# lamloei_umo32c_r2_1.net
KiCad netlist of a schematic drawn in EAGLE
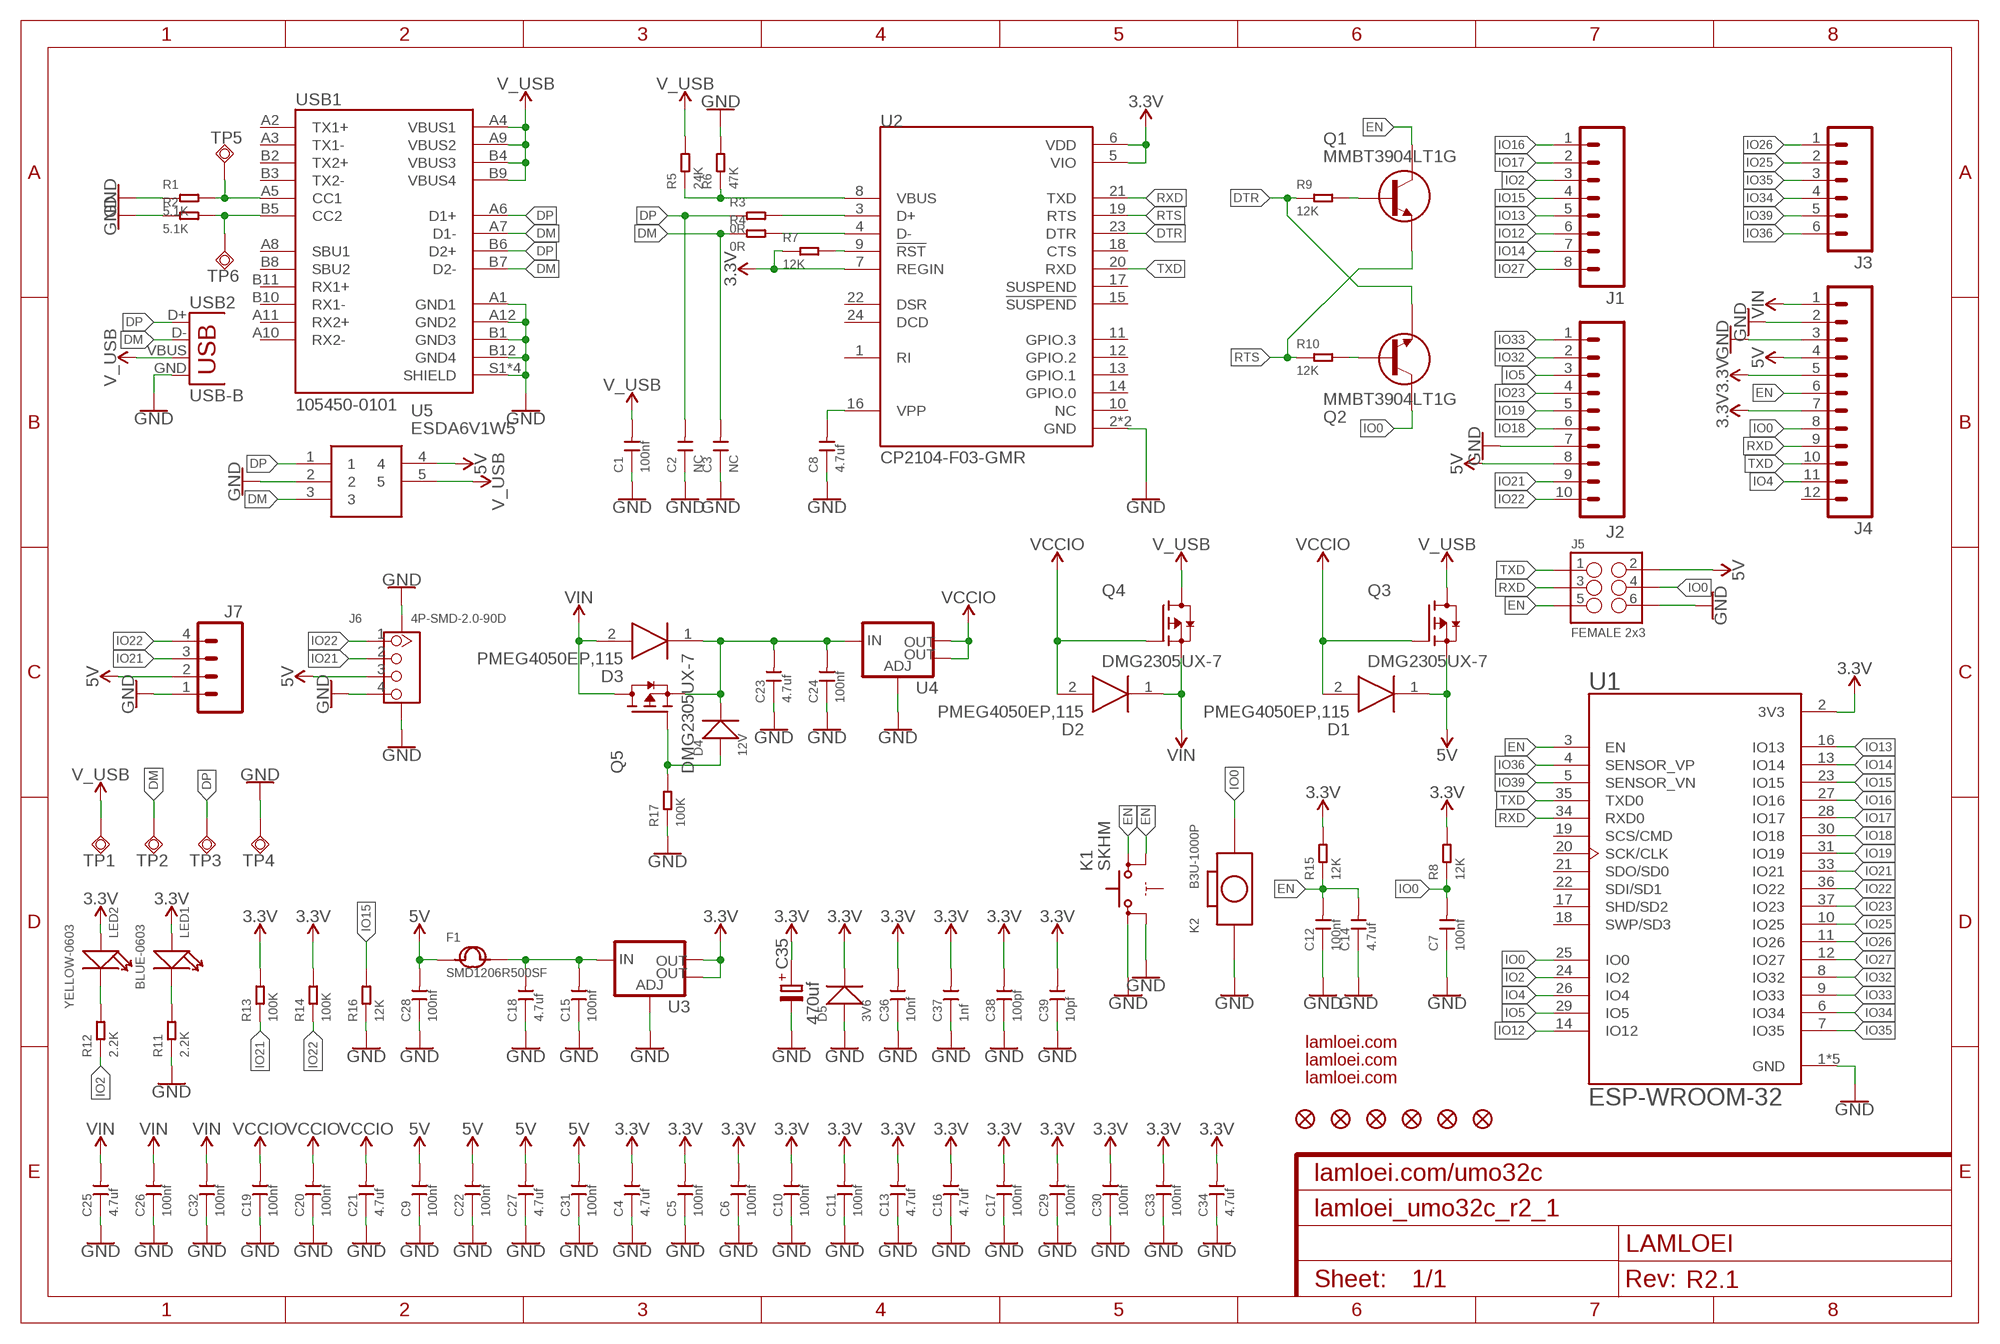
[diagram p0: schematic, sheet 1]

(export (version "E")
  (design (tool "Eeschema 10.0.6"))
  (components
    (comp (ref "C1")
      (value "100nf")
      (footprint "eagle-import:C0402")
      (fields (field (name "MPN") "CC0402KRX7R8BB104"))
      (libsource (lib "eagle-import") (part "CERAMIC-100NF-25V-10%-X7R(0402)"))
    )
    (comp (ref "C2")
      (value "NC")
      (footprint "eagle-import:C0402")
      (fields (field (name "MPN") "CC0402JRNPO9BN470"))
      (libsource (lib "eagle-import") (part "CERAMIC-47PF-50V-5%-NP0(0402)"))
    )
    (comp (ref "C3")
      (value "NC")
      (footprint "eagle-import:C0402")
      (fields (field (name "MPN") "CC0402JRNPO9BN470"))
      (libsource (lib "eagle-import") (part "CERAMIC-47PF-50V-5%-NP0(0402)"))
    )
    (comp (ref "C4")
      (value "4.7uf")
      (footprint "eagle-import:C0805")
      (fields (field (name "MPN") "CC0805KKX5R8BB106"))
      (libsource (lib "eagle-import") (part "CERAMIC-10UF-25V-10%-X5R(0805)"))
    )
    (comp (ref "C5")
      (value "100nf")
      (footprint "eagle-import:C0402")
      (fields (field (name "MPN") "CC0402KRX7R8BB104"))
      (libsource (lib "eagle-import") (part "CERAMIC-100NF-25V-10%-X7R(0402)"))
    )
    (comp (ref "C6")
      (value "100nf")
      (footprint "eagle-import:C0402")
      (fields (field (name "MPN") "CC0402KRX7R8BB104"))
      (libsource (lib "eagle-import") (part "CERAMIC-100NF-25V-10%-X7R(0402)"))
    )
    (comp (ref "C7")
      (value "100nf")
      (footprint "eagle-import:C0402")
      (fields (field (name "MPN") "CC0402KRX7R8BB104"))
      (libsource (lib "eagle-import") (part "CERAMIC-100NF-25V-10%-X7R(0402)"))
    )
    (comp (ref "C8")
      (value "4.7uf")
      (footprint "eagle-import:C0805")
      (fields (field (name "MPN") "CC0805KKX5R8BB106"))
      (libsource (lib "eagle-import") (part "CERAMIC-10UF-25V-10%-X5R(0805)"))
    )
    (comp (ref "C9")
      (value "100nf")
      (footprint "eagle-import:C0402")
      (fields (field (name "MPN") "CC0402KRX7R8BB104"))
      (libsource (lib "eagle-import") (part "CERAMIC-100NF-25V-10%-X7R(0402)"))
    )
    (comp (ref "C10")
      (value "100nf")
      (footprint "eagle-import:C0402")
      (fields (field (name "MPN") "CC0402KRX7R8BB104"))
      (libsource (lib "eagle-import") (part "CERAMIC-100NF-25V-10%-X7R(0402)"))
    )
    (comp (ref "C11")
      (value "100nf")
      (footprint "eagle-import:C0402")
      (fields (field (name "MPN") "CC0402KRX7R8BB104"))
      (libsource (lib "eagle-import") (part "CERAMIC-100NF-25V-10%-X7R(0402)"))
    )
    (comp (ref "C12")
      (value "100nf")
      (footprint "eagle-import:C0402")
      (fields (field (name "MPN") "CC0402KRX7R8BB104"))
      (libsource (lib "eagle-import") (part "CERAMIC-100NF-25V-10%-X7R(0402)"))
    )
    (comp (ref "C13")
      (value "4.7uf")
      (footprint "eagle-import:C0805")
      (fields (field (name "MPN") "CC0805KKX5R8BB106"))
      (libsource (lib "eagle-import") (part "CERAMIC-10UF-25V-10%-X5R(0805)"))
    )
    (comp (ref "C14")
      (value "4.7uf")
      (footprint "eagle-import:C0805")
      (fields (field (name "MPN") "CC0805KKX5R8BB106"))
      (libsource (lib "eagle-import") (part "CERAMIC-10UF-25V-10%-X5R(0805)"))
    )
    (comp (ref "C15")
      (value "100nf")
      (footprint "eagle-import:C0402")
      (fields (field (name "MPN") "CC0402KRX7R8BB104"))
      (libsource (lib "eagle-import") (part "CERAMIC-100NF-25V-10%-X7R(0402)"))
    )
    (comp (ref "C16")
      (value "4.7uf")
      (footprint "eagle-import:C0805")
      (fields (field (name "MPN") "CC0805KKX5R8BB106"))
      (libsource (lib "eagle-import") (part "CERAMIC-10UF-25V-10%-X5R(0805)"))
    )
    (comp (ref "C17")
      (value "100nf")
      (footprint "eagle-import:C0402")
      (fields (field (name "MPN") "CC0402KRX7R8BB104"))
      (libsource (lib "eagle-import") (part "CERAMIC-100NF-25V-10%-X7R(0402)"))
    )
    (comp (ref "C18")
      (value "4.7uf")
      (footprint "eagle-import:C0805")
      (fields (field (name "MPN") "CC0805KKX5R8BB106"))
      (libsource (lib "eagle-import") (part "CERAMIC-10UF-25V-10%-X5R(0805)"))
    )
    (comp (ref "C19")
      (value "100nf")
      (footprint "eagle-import:C0402")
      (fields (field (name "MPN") "CC0402KRX7R8BB104"))
      (libsource (lib "eagle-import") (part "CERAMIC-100NF-25V-10%-X7R(0402)"))
    )
    (comp (ref "C20")
      (value "100nf")
      (footprint "eagle-import:C0402")
      (fields (field (name "MPN") "CC0402KRX7R8BB104"))
      (libsource (lib "eagle-import") (part "CERAMIC-100NF-25V-10%-X7R(0402)"))
    )
    (comp (ref "C21")
      (value "4.7uf")
      (footprint "eagle-import:C0805")
      (fields (field (name "MPN") "CC0805KKX5R8BB106"))
      (libsource (lib "eagle-import") (part "CERAMIC-10UF-25V-10%-X5R(0805)"))
    )
    (comp (ref "C22")
      (value "100nf")
      (footprint "eagle-import:C0402")
      (fields (field (name "MPN") "CC0402KRX7R8BB104"))
      (libsource (lib "eagle-import") (part "CERAMIC-100NF-25V-10%-X7R(0402)"))
    )
    (comp (ref "C23")
      (value "4.7uf")
      (footprint "eagle-import:C0805")
      (fields (field (name "MPN") "CC0805KKX5R8BB106"))
      (libsource (lib "eagle-import") (part "CERAMIC-10UF-25V-10%-X5R(0805)"))
    )
    (comp (ref "C24")
      (value "100nf")
      (footprint "eagle-import:C0402")
      (fields (field (name "MPN") "CC0402KRX7R8BB104"))
      (libsource (lib "eagle-import") (part "CERAMIC-100NF-25V-10%-X7R(0402)"))
    )
    (comp (ref "C25")
      (value "4.7uf")
      (footprint "eagle-import:C0805")
      (fields (field (name "MPN") "CC0805KKX5R8BB106"))
      (libsource (lib "eagle-import") (part "CERAMIC-10UF-25V-10%-X5R(0805)"))
    )
    (comp (ref "C26")
      (value "100nf")
      (footprint "eagle-import:C0402")
      (fields (field (name "MPN") "CC0402KRX7R8BB104"))
      (libsource (lib "eagle-import") (part "CERAMIC-100NF-25V-10%-X7R(0402)"))
    )
    (comp (ref "C27")
      (value "4.7uf")
      (footprint "eagle-import:C0805")
      (fields (field (name "MPN") "CC0805KKX5R8BB106"))
      (libsource (lib "eagle-import") (part "CERAMIC-10UF-25V-10%-X5R(0805)"))
    )
    (comp (ref "C28")
      (value "100nf")
      (footprint "eagle-import:C0402")
      (fields (field (name "MPN") "CC0402KRX7R8BB104"))
      (libsource (lib "eagle-import") (part "CERAMIC-100NF-25V-10%-X7R(0402)"))
    )
    (comp (ref "C29")
      (value "100nf")
      (footprint "eagle-import:C0402")
      (fields (field (name "MPN") "CC0402KRX7R8BB104"))
      (libsource (lib "eagle-import") (part "CERAMIC-100NF-25V-10%-X7R(0402)"))
    )
    (comp (ref "C30")
      (value "100nf")
      (footprint "eagle-import:C0402")
      (fields (field (name "MPN") "CC0402KRX7R8BB104"))
      (libsource (lib "eagle-import") (part "CERAMIC-100NF-25V-10%-X7R(0402)"))
    )
    (comp (ref "C31")
      (value "100nf")
      (footprint "eagle-import:C0402")
      (fields (field (name "MPN") "CC0402KRX7R8BB104"))
      (libsource (lib "eagle-import") (part "CERAMIC-100NF-25V-10%-X7R(0402)"))
    )
    (comp (ref "C32")
      (value "100nf")
      (footprint "eagle-import:C0402")
      (fields (field (name "MPN") "CC0402KRX7R8BB104"))
      (libsource (lib "eagle-import") (part "CERAMIC-100NF-25V-10%-X7R(0402)"))
    )
    (comp (ref "C33")
      (value "100nf")
      (footprint "eagle-import:C0402")
      (fields (field (name "MPN") "CC0402KRX7R8BB104"))
      (libsource (lib "eagle-import") (part "CERAMIC-100NF-25V-10%-X7R(0402)"))
    )
    (comp (ref "C34")
      (value "4.7uf")
      (footprint "eagle-import:C0805")
      (fields (field (name "MPN") "CC0805KKX5R8BB106"))
      (libsource (lib "eagle-import") (part "CERAMIC-10UF-25V-10%-X5R(0805)"))
    )
    (comp (ref "C35")
      (value "470uf")
      (footprint "eagle-import:TE-D-7343")
      (libsource (lib "eagle-import") (part "C-PR-SMD-TE-D"))
    )
    (comp (ref "C36")
      (value "10nf")
      (footprint "eagle-import:C0402")
      (fields (field (name "MPN") "CC0402KRX7R8BB104"))
      (libsource (lib "eagle-import") (part "CERAMIC-100NF-25V-10%-X7R(0402)"))
    )
    (comp (ref "C37")
      (value "1nf")
      (footprint "eagle-import:C0402")
      (fields (field (name "MPN") "CC0402KRX7R8BB104"))
      (libsource (lib "eagle-import") (part "CERAMIC-100NF-25V-10%-X7R(0402)"))
    )
    (comp (ref "C38")
      (value "100pf")
      (footprint "eagle-import:C0402")
      (fields (field (name "MPN") "CC0402KRX7R8BB104"))
      (libsource (lib "eagle-import") (part "CERAMIC-100NF-25V-10%-X7R(0402)"))
    )
    (comp (ref "C39")
      (value "10pf")
      (footprint "eagle-import:C0402")
      (fields (field (name "MPN") "CC0402KRX7R8BB104"))
      (libsource (lib "eagle-import") (part "CERAMIC-100NF-25V-10%-X7R(0402)"))
    )
    (comp (ref "D1")
      (value "PMEG4050EP,115")
      (footprint "eagle-import:SODFL4725X110N")
      (fields (field (name "RS_PART_NUMBER") "7805405P"))
      (libsource (lib "eagle-import") (part "PMEG4050EP,115"))
    )
    (comp (ref "D2")
      (value "PMEG4050EP,115")
      (footprint "eagle-import:SODFL4725X110N")
      (fields (field (name "RS_PART_NUMBER") "7805405P"))
      (libsource (lib "eagle-import") (part "PMEG4050EP,115"))
    )
    (comp (ref "D3")
      (value "PMEG4050EP,115")
      (footprint "eagle-import:SODFL4725X110N")
      (fields (field (name "RS_PART_NUMBER") "7805405P"))
      (libsource (lib "eagle-import") (part "PMEG4050EP,115"))
    )
    (comp (ref "D4")
      (value "12V")
      (footprint "eagle-import:LL-34")
      (libsource (lib "eagle-import") (part "DIODE'1N4148-SMD'"))
    )
    (comp (ref "D5")
      (value "3V6")
      (footprint "eagle-import:LL-34")
      (libsource (lib "eagle-import") (part "DIODE'1N4148-SMD'"))
    )
    (comp (ref "F1")
      (value "SMD1206R500SF")
      (footprint "eagle-import:F1206")
      (libsource (lib "eagle-import") (part "SMD-PPTC-500MA(1206)"))
    )
    (comp (ref "J1")
      (value "M08SILK_FEMALE_PTH")
      (footprint "eagle-import:1X08")
      (libsource (lib "eagle-import") (part "M08SILK_FEMALE_PTH"))
    )
    (comp (ref "J2")
      (value "M10SILK_FEMALE_PTH")
      (footprint "eagle-import:1X10")
      (libsource (lib "eagle-import") (part "M10SILK_FEMALE_PTH"))
    )
    (comp (ref "J3")
      (value "M06SILK_FEMALE_PTH")
      (footprint "eagle-import:1X06")
      (libsource (lib "eagle-import") (part "M06SILK_FEMALE_PTH"))
    )
    (comp (ref "J4")
      (value "M12PTH")
      (footprint "eagle-import:1X12")
      (libsource (lib "eagle-import") (part "M12PTH"))
    )
    (comp (ref "J5")
      (value "FEMALE 2x3")
      (footprint "eagle-import:2X3")
      (libsource (lib "eagle-import") (part "M03X2FEMALE"))
    )
    (comp (ref "J6")
      (value "4P-SMD-2.0-90D")
      (footprint "eagle-import:HW4-SMD-2.0-90D")
      (libsource (lib "eagle-import") (part "GROVE-CONNECTOR-SMD-90D(4+2P-2.0)"))
    )
    (comp (ref "J7")
      (value "M04LONGPADS")
      (footprint "eagle-import:1X04_LONGPADS")
      (libsource (lib "eagle-import") (part "M04LONGPADS"))
    )
    (comp (ref "K1")
      (value "SKHM")
      (footprint "eagle-import:SKHM")
      (libsource (lib "eagle-import") (part "SKHM"))
    )
    (comp (ref "K2")
      (value "B3U-1000P")
      (footprint "eagle-import:SW2-SMD-3.0X2.5X1.2+0.4MM")
      (libsource (lib "eagle-import") (part "SMD-BUTTON-WITHOUT-BOSS-(2P-3X2.5MM)"))
    )
    (comp (ref "LED1")
      (value "BLUE-0603")
      (footprint "eagle-import:LED-0603")
      (fields (field (name "MPN") "19-217-BHC-ZL1M2RY-3T"))
      (libsource (lib "eagle-import") (part "SMD-LED-CLEAR-BLUE(0603)"))
    )
    (comp (ref "LED2")
      (value "YELLOW-0603")
      (footprint "eagle-import:LED-0603")
      (fields (field (name "MPN") "19-217-BHC-ZL1M2RY-3T"))
      (libsource (lib "eagle-import") (part "SMD-LED-CLEAR-BLUE(0603)"))
    )
    (comp (ref "Q1")
      (value "MMBT3904LT1G")
      (footprint "eagle-import:SOT23")
      (fields (field (name "MF") "ON Semiconductor"))
      (libsource (lib "eagle-import") (part "MMBT3904LT1G"))
    )
    (comp (ref "Q2")
      (value "MMBT3904LT1G")
      (footprint "eagle-import:SOT23")
      (fields (field (name "MF") "ON Semiconductor"))
      (libsource (lib "eagle-import") (part "MMBT3904LT1G"))
    )
    (comp (ref "Q3")
      (value "DMG2305UX-7")
      (footprint "eagle-import:SOT91P240X110-3N_DMG2305UX-7")
      (fields (field (name "MF") "Diodes Inc."))
      (libsource (lib "eagle-import") (part "DMG2305UX-7"))
    )
    (comp (ref "Q4")
      (value "DMG2305UX-7")
      (footprint "eagle-import:SOT91P240X110-3N_DMG2305UX-7")
      (fields (field (name "MF") "Diodes Inc."))
      (libsource (lib "eagle-import") (part "DMG2305UX-7"))
    )
    (comp (ref "Q5")
      (value "DMG2305UX-7")
      (footprint "eagle-import:SOT91P240X110-3N_DMG2305UX-7")
      (fields (field (name "MF") "Diodes Inc."))
      (libsource (lib "eagle-import") (part "DMG2305UX-7"))
    )
    (comp (ref "R1")
      (value "5.1K")
      (footprint "eagle-import:R0402")
      (fields (field (name "MPN") "RC0402JR-074K7L"))
      (libsource (lib "eagle-import") (part "SMD-RES-4.7K-5%-1/16W(0402)"))
    )
    (comp (ref "R2")
      (value "5.1K")
      (footprint "eagle-import:R0402")
      (fields (field (name "MPN") "RC0402JR-074K7L"))
      (libsource (lib "eagle-import") (part "SMD-RES-4.7K-5%-1/16W(0402)"))
    )
    (comp (ref "R3")
      (value "0R")
      (footprint "eagle-import:R0402")
      (fields (field (name "MPN") "RC0402FR-0722RL"))
      (libsource (lib "eagle-import") (part "SMD-RES-22R-1%-1/16W(0402)"))
    )
    (comp (ref "R4")
      (value "0R")
      (footprint "eagle-import:R0402")
      (fields (field (name "MPN") "RC0402FR-0722RL"))
      (libsource (lib "eagle-import") (part "SMD-RES-22R-1%-1/16W(0402)"))
    )
    (comp (ref "R5")
      (value "24K")
      (footprint "eagle-import:R0402")
      (fields (field (name "MPN") "RC0402FR-0722RL"))
      (libsource (lib "eagle-import") (part "SMD-RES-22R-1%-1/16W(0402)"))
    )
    (comp (ref "R6")
      (value "47K")
      (footprint "eagle-import:R0402")
      (fields (field (name "MPN") "RC0402FR-0722RL"))
      (libsource (lib "eagle-import") (part "SMD-RES-22R-1%-1/16W(0402)"))
    )
    (comp (ref "R7")
      (value "12K")
      (footprint "eagle-import:R0402")
      (fields (field (name "MPN") "RC0402FR-0710KL"))
      (libsource (lib "eagle-import") (part "SMD-RES-10K-1%-1/16W(0402)"))
    )
    (comp (ref "R8")
      (value "12K")
      (footprint "eagle-import:R0402")
      (fields (field (name "MPN") "RC0402FR-0710KL"))
      (libsource (lib "eagle-import") (part "SMD-RES-10K-1%-1/16W(0402)"))
    )
    (comp (ref "R9")
      (value "12K")
      (footprint "eagle-import:R0402")
      (fields (field (name "MPN") "RC0402FR-0710KL"))
      (libsource (lib "eagle-import") (part "SMD-RES-10K-1%-1/16W(0402)"))
    )
    (comp (ref "R10")
      (value "12K")
      (footprint "eagle-import:R0402")
      (fields (field (name "MPN") "RC0402FR-0710KL"))
      (libsource (lib "eagle-import") (part "SMD-RES-10K-1%-1/16W(0402)"))
    )
    (comp (ref "R11")
      (value "2.2K")
      (footprint "eagle-import:R0402")
      (fields (field (name "MPN") "RC0402FR-072K7L"))
      (libsource (lib "eagle-import") (part "SMD-RES-2.7K-1%-1/16W(0402)"))
    )
    (comp (ref "R12")
      (value "2.2K")
      (footprint "eagle-import:R0402")
      (fields (field (name "MPN") "RC0402FR-072K7L"))
      (libsource (lib "eagle-import") (part "SMD-RES-2.7K-1%-1/16W(0402)"))
    )
    (comp (ref "R13")
      (value "100K")
      (footprint "eagle-import:R0402")
      (fields (field (name "MPN") "RC0402FR-0710KL"))
      (libsource (lib "eagle-import") (part "SMD-RES-10K-1%-1/16W(0402)"))
    )
    (comp (ref "R14")
      (value "100K")
      (footprint "eagle-import:R0402")
      (fields (field (name "MPN") "RC0402FR-0710KL"))
      (libsource (lib "eagle-import") (part "SMD-RES-10K-1%-1/16W(0402)"))
    )
    (comp (ref "R15")
      (value "12K")
      (footprint "eagle-import:R0402")
      (fields (field (name "MPN") "RC0402FR-0710KL"))
      (libsource (lib "eagle-import") (part "SMD-RES-10K-1%-1/16W(0402)"))
    )
    (comp (ref "R16")
      (value "12K")
      (footprint "eagle-import:R0402")
      (fields (field (name "MPN") "RC0402FR-0710KL"))
      (libsource (lib "eagle-import") (part "SMD-RES-10K-1%-1/16W(0402)"))
    )
    (comp (ref "R17")
      (value "100K")
      (footprint "eagle-import:R0402")
      (fields (field (name "MPN") "RC0402FR-0710KL"))
      (libsource (lib "eagle-import") (part "SMD-RES-10K-1%-1/16W(0402)"))
    )
    (comp (ref "TP1")
      (value "TPSQTP13SQ")
      (footprint "eagle-import:TP13SQ")
      (libsource (lib "eagle-import") (part "TPSQTP13SQ"))
    )
    (comp (ref "TP2")
      (value "TPSQTP13SQ")
      (footprint "eagle-import:TP13SQ")
      (libsource (lib "eagle-import") (part "TPSQTP13SQ"))
    )
    (comp (ref "TP3")
      (value "TPSQTP13SQ")
      (footprint "eagle-import:TP13SQ")
      (libsource (lib "eagle-import") (part "TPSQTP13SQ"))
    )
    (comp (ref "TP4")
      (value "TPSQTP13SQ")
      (footprint "eagle-import:TP13SQ")
      (libsource (lib "eagle-import") (part "TPSQTP13SQ"))
    )
    (comp (ref "TP5")
      (value "TPSQTP13SQ")
      (footprint "eagle-import:TP13SQ")
      (libsource (lib "eagle-import") (part "TPSQTP13SQ"))
    )
    (comp (ref "TP6")
      (value "TPSQTP13SQ")
      (footprint "eagle-import:TP13SQ")
      (libsource (lib "eagle-import") (part "TPSQTP13SQ"))
    )
    (comp (ref "U1")
      (value "ESP-WROOM-32")
      (footprint "eagle-import:MODULE_ESP-WROOM-32")
      (fields (field (name "MF") "Olimex LTD"))
      (libsource (lib "eagle-import") (part "ESP-WROOM-32"))
    )
    (comp (ref "U2")
      (value "CP2104-F03-GMR")
      (footprint "eagle-import:CP2104-F03-GMR")
      (fields (field (name "LCSC_PART") "C47742") (field (name "MF") "Silicon Labs"))
      (libsource (lib "eagle-import") (part "CP2104-F03-GMR"))
    )
    (comp (ref "U3")
      (value "V_REG_LM1117SOT223")
      (footprint "eagle-import:SOT223")
      (libsource (lib "eagle-import") (part "V_REG_LM1117SOT223"))
    )
    (comp (ref "U4")
      (value "V_REG_LM1117SOT223")
      (footprint "eagle-import:SOT223")
      (libsource (lib "eagle-import") (part "V_REG_LM1117SOT223"))
    )
    (comp (ref "U5")
      (value "ESDA6V1W5")
      (footprint "eagle-import:SOT65P210X110-5N")
      (fields (field (name "RS_PART_NUMBER") "1685770"))
      (libsource (lib "eagle-import") (part "ESDA6V1W5"))
    )
    (comp (ref "USB1")
      (value "105450-0101")
      (footprint "eagle-import:105450-0101")
      (fields (field (name "MF") "Molex"))
      (libsource (lib "eagle-import") (part "105450-0101"))
    )
    (comp (ref "USB2")
      (value "USB-B")
      (footprint "eagle-import:USB-B-PTH")
      (libsource (lib "eagle-import") (part "USBPTH"))
    )
    (comp (ref "ZFC1")
      (value "FIDUCIAL1X2")
      (footprint "eagle-import:FIDUCIAL-1X2")
      (libsource (lib "eagle-import") (part "FIDUCIAL1X2"))
    )
    (comp (ref "ZFC2")
      (value "FIDUCIAL1X2")
      (footprint "eagle-import:FIDUCIAL-1X2")
      (libsource (lib "eagle-import") (part "FIDUCIAL1X2"))
    )
    (comp (ref "ZFC3")
      (value "FIDUCIAL1X2")
      (footprint "eagle-import:FIDUCIAL-1X2")
      (libsource (lib "eagle-import") (part "FIDUCIAL1X2"))
    )
    (comp (ref "ZFD1")
      (value "FIDUCIAL1X2")
      (footprint "eagle-import:FIDUCIAL-1X2")
      (libsource (lib "eagle-import") (part "FIDUCIAL1X2"))
    )
    (comp (ref "ZFD2")
      (value "FIDUCIAL1X2")
      (footprint "eagle-import:FIDUCIAL-1X2")
      (libsource (lib "eagle-import") (part "FIDUCIAL1X2"))
    )
    (comp (ref "ZFD3")
      (value "FIDUCIAL1X2")
      (footprint "eagle-import:FIDUCIAL-1X2")
      (libsource (lib "eagle-import") (part "FIDUCIAL1X2"))
    )
    (comp (ref "ZL1")
      (value "LAMLEOI_LOGO_3")
      (footprint "eagle-import:LAMLEOI_LOGO_3")
      (libsource (lib "eagle-import") (part "LAMLEOI_LOGO_3"))
    )
    (comp (ref "ZL2")
      (value "LAMLEOI_LOGO_3")
      (footprint "eagle-import:LAMLEOI_LOGO_3")
      (libsource (lib "eagle-import") (part "LAMLEOI_LOGO_3"))
    )
    (comp (ref "ZL3")
      (value "LAMLOEI_BIGLOGO")
      (footprint "eagle-import:LAMLOEI_BIGLOGO")
      (libsource (lib "eagle-import") (part "LAMLOEI_BIGLOGO"))
    )
  )
  (nets
    (net (code "1") (name "3.3V") (class "Default")
      (node (ref "C10") (pin "2") (pinfunction "2_2") (pintype "passive"))
      (node (ref "C11") (pin "2") (pinfunction "2_2") (pintype "passive"))
      (node (ref "C13") (pin "2") (pinfunction "2_2") (pintype "passive"))
      (node (ref "C16") (pin "2") (pinfunction "2_2") (pintype "passive"))
      (node (ref "C17") (pin "2") (pinfunction "2_2") (pintype "passive"))
      (node (ref "C29") (pin "2") (pinfunction "2_2") (pintype "passive"))
      (node (ref "C30") (pin "2") (pinfunction "2_2") (pintype "passive"))
      (node (ref "C33") (pin "2") (pinfunction "2_2") (pintype "passive"))
      (node (ref "C34") (pin "2") (pinfunction "2_2") (pintype "passive"))
      (node (ref "C35") (pin "+") (pinfunction "+_+") (pintype "passive"))
      (node (ref "C36") (pin "2") (pinfunction "2_2") (pintype "passive"))
      (node (ref "C37") (pin "2") (pinfunction "2_2") (pintype "passive"))
      (node (ref "C38") (pin "2") (pinfunction "2_2") (pintype "passive"))
      (node (ref "C39") (pin "2") (pinfunction "2_2") (pintype "passive"))
      (node (ref "C4") (pin "2") (pinfunction "2_2") (pintype "passive"))
      (node (ref "C5") (pin "2") (pinfunction "2_2") (pintype "passive"))
      (node (ref "C6") (pin "2") (pinfunction "2_2") (pintype "passive"))
      (node (ref "D5") (pin "C") (pinfunction "-_C") (pintype "passive"))
      (node (ref "J4") (pin "5") (pinfunction "5_5") (pintype "passive"))
      (node (ref "J4") (pin "7") (pinfunction "7_7") (pintype "passive"))
      (node (ref "LED1") (pin "+") (pinfunction "+_+") (pintype "passive"))
      (node (ref "LED2") (pin "+") (pinfunction "+_+") (pintype "passive"))
      (node (ref "R13") (pin "2") (pinfunction "2_2") (pintype "passive"))
      (node (ref "R14") (pin "2") (pinfunction "2_2") (pintype "passive"))
      (node (ref "R15") (pin "2") (pinfunction "2_2") (pintype "passive"))
      (node (ref "R7") (pin "1") (pinfunction "1_1") (pintype "passive"))
      (node (ref "R8") (pin "2") (pinfunction "2_2") (pintype "passive"))
      (node (ref "U1") (pin "2") (pinfunction "3V3_2") (pintype "power_in"))
      (node (ref "U2") (pin "5") (pinfunction "VIO_5") (pintype "power_in"))
      (node (ref "U2") (pin "6") (pinfunction "VDD_6") (pintype "power_in"))
      (node (ref "U2") (pin "7") (pinfunction "REGIN_7") (pintype "input"))
      (node (ref "U3") (pin "2") (pinfunction "OUT_2") (pintype "output"))
      (node (ref "U3") (pin "4") (pinfunction "OUT_4") (pintype "output"))
    )
    (net (code "2") (name "5V") (class "Default")
      (node (ref "C22") (pin "2") (pinfunction "2_2") (pintype "passive"))
      (node (ref "C27") (pin "2") (pinfunction "2_2") (pintype "passive"))
      (node (ref "C28") (pin "2") (pinfunction "2_2") (pintype "passive"))
      (node (ref "C31") (pin "2") (pinfunction "2_2") (pintype "passive"))
      (node (ref "C9") (pin "2") (pinfunction "2_2") (pintype "passive"))
      (node (ref "D1") (pin "1") (pinfunction "K_1") (pintype "bidirectional"))
      (node (ref "F1") (pin "1") (pinfunction "1_1") (pintype "bidirectional"))
      (node (ref "J2") (pin "8") (pinfunction "8_8") (pintype "passive"))
      (node (ref "J4") (pin "4") (pinfunction "4_4") (pintype "passive"))
      (node (ref "J5") (pin "2") (pinfunction "2_2") (pintype "bidirectional"))
      (node (ref "J6") (pin "3") (pinfunction "3_3") (pintype "bidirectional"))
      (node (ref "J7") (pin "2") (pinfunction "2_2") (pintype "passive"))
      (node (ref "Q3") (pin "2") (pinfunction "S_2") (pintype "passive"))
      (node (ref "U5") (pin "4") (pinfunction "4_4") (pintype "bidirectional"))
    )
    (net (code "3") (name "DM") (class "Default")
      (node (ref "C3") (pin "2") (pinfunction "2_2") (pintype "passive"))
      (node (ref "R4") (pin "1") (pinfunction "1_1") (pintype "passive"))
      (node (ref "TP2") (pin "TP") (pinfunction "TP_TP") (pintype "input"))
      (node (ref "U5") (pin "3") (pinfunction "3_3") (pintype "bidirectional"))
      (node (ref "USB1") (pin "A7") (pinfunction "D1-_A7") (pintype "passive"))
      (node (ref "USB1") (pin "B7") (pinfunction "D2-_B7") (pintype "passive"))
      (node (ref "USB2") (pin "D-") (pinfunction "D-_D-") (pintype "bidirectional"))
    )
    (net (code "4") (name "DP") (class "Default")
      (node (ref "C2") (pin "2") (pinfunction "2_2") (pintype "passive"))
      (node (ref "R3") (pin "1") (pinfunction "1_1") (pintype "passive"))
      (node (ref "TP3") (pin "TP") (pinfunction "TP_TP") (pintype "input"))
      (node (ref "U5") (pin "1") (pinfunction "1_1") (pintype "bidirectional"))
      (node (ref "USB1") (pin "A6") (pinfunction "D1+_A6") (pintype "passive"))
      (node (ref "USB1") (pin "B6") (pinfunction "D2+_B6") (pintype "passive"))
      (node (ref "USB2") (pin "D+") (pinfunction "D+_D+") (pintype "bidirectional"))
    )
    (net (code "5") (name "DTR") (class "Default")
      (node (ref "Q2") (pin "2") (pinfunction "E_2") (pintype "passive"))
      (node (ref "R9") (pin "1") (pinfunction "1_1") (pintype "passive"))
      (node (ref "U2") (pin "23") (pinfunction "DTR_23") (pintype "output"))
    )
    (net (code "6") (name "EN") (class "Default")
      (node (ref "C12") (pin "2") (pinfunction "2_2") (pintype "passive"))
      (node (ref "C14") (pin "2") (pinfunction "2_2") (pintype "passive"))
      (node (ref "J4") (pin "6") (pinfunction "6_6") (pintype "passive"))
      (node (ref "J5") (pin "5") (pinfunction "5_5") (pintype "bidirectional"))
      (node (ref "K1") (pin "3") (pinfunction "S1_3") (pintype "passive"))
      (node (ref "K1") (pin "4") (pinfunction "S2_4") (pintype "passive"))
      (node (ref "Q1") (pin "3") (pinfunction "C_3") (pintype "passive"))
      (node (ref "R15") (pin "1") (pinfunction "1_1") (pintype "passive"))
      (node (ref "U1") (pin "3") (pinfunction "EN_3") (pintype "input"))
    )
    (net (code "7") (name "GND") (class "Default")
      (node (ref "C1") (pin "1") (pinfunction "1_1") (pintype "passive"))
      (node (ref "C10") (pin "1") (pinfunction "1_1") (pintype "passive"))
      (node (ref "C11") (pin "1") (pinfunction "1_1") (pintype "passive"))
      (node (ref "C12") (pin "1") (pinfunction "1_1") (pintype "passive"))
      (node (ref "C13") (pin "1") (pinfunction "1_1") (pintype "passive"))
      (node (ref "C14") (pin "1") (pinfunction "1_1") (pintype "passive"))
      (node (ref "C15") (pin "1") (pinfunction "1_1") (pintype "passive"))
      (node (ref "C16") (pin "1") (pinfunction "1_1") (pintype "passive"))
      (node (ref "C17") (pin "1") (pinfunction "1_1") (pintype "passive"))
      (node (ref "C18") (pin "1") (pinfunction "1_1") (pintype "passive"))
      (node (ref "C19") (pin "1") (pinfunction "1_1") (pintype "passive"))
      (node (ref "C2") (pin "1") (pinfunction "1_1") (pintype "passive"))
      (node (ref "C20") (pin "1") (pinfunction "1_1") (pintype "passive"))
      (node (ref "C21") (pin "1") (pinfunction "1_1") (pintype "passive"))
      (node (ref "C22") (pin "1") (pinfunction "1_1") (pintype "passive"))
      (node (ref "C23") (pin "1") (pinfunction "1_1") (pintype "passive"))
      (node (ref "C24") (pin "1") (pinfunction "1_1") (pintype "passive"))
      (node (ref "C25") (pin "1") (pinfunction "1_1") (pintype "passive"))
      (node (ref "C26") (pin "1") (pinfunction "1_1") (pintype "passive"))
      (node (ref "C27") (pin "1") (pinfunction "1_1") (pintype "passive"))
      (node (ref "C28") (pin "1") (pinfunction "1_1") (pintype "passive"))
      (node (ref "C29") (pin "1") (pinfunction "1_1") (pintype "passive"))
      (node (ref "C3") (pin "1") (pinfunction "1_1") (pintype "passive"))
      (node (ref "C30") (pin "1") (pinfunction "1_1") (pintype "passive"))
      (node (ref "C31") (pin "1") (pinfunction "1_1") (pintype "passive"))
      (node (ref "C32") (pin "1") (pinfunction "1_1") (pintype "passive"))
      (node (ref "C33") (pin "1") (pinfunction "1_1") (pintype "passive"))
      (node (ref "C34") (pin "1") (pinfunction "1_1") (pintype "passive"))
      (node (ref "C35") (pin "-") (pinfunction "-_-") (pintype "passive"))
      (node (ref "C36") (pin "1") (pinfunction "1_1") (pintype "passive"))
      (node (ref "C37") (pin "1") (pinfunction "1_1") (pintype "passive"))
      (node (ref "C38") (pin "1") (pinfunction "1_1") (pintype "passive"))
      (node (ref "C39") (pin "1") (pinfunction "1_1") (pintype "passive"))
      (node (ref "C4") (pin "1") (pinfunction "1_1") (pintype "passive"))
      (node (ref "C5") (pin "1") (pinfunction "1_1") (pintype "passive"))
      (node (ref "C6") (pin "1") (pinfunction "1_1") (pintype "passive"))
      (node (ref "C7") (pin "1") (pinfunction "1_1") (pintype "passive"))
      (node (ref "C8") (pin "1") (pinfunction "1_1") (pintype "passive"))
      (node (ref "C9") (pin "1") (pinfunction "1_1") (pintype "passive"))
      (node (ref "D5") (pin "A") (pinfunction "+_A") (pintype "passive"))
      (node (ref "J2") (pin "7") (pinfunction "7_7") (pintype "passive"))
      (node (ref "J4") (pin "2") (pinfunction "2_2") (pintype "passive"))
      (node (ref "J4") (pin "3") (pinfunction "3_3") (pintype "passive"))
      (node (ref "J5") (pin "6") (pinfunction "6_6") (pintype "bidirectional"))
      (node (ref "J6") (pin "4") (pinfunction "4_4") (pintype "bidirectional"))
      (node (ref "J6") (pin "SS1") (pinfunction "SS1_SS1") (pintype "bidirectional"))
      (node (ref "J6") (pin "SS2") (pinfunction "SS2_SS2") (pintype "bidirectional"))
      (node (ref "J7") (pin "1") (pinfunction "1_1") (pintype "passive"))
      (node (ref "K1") (pin "1") (pinfunction "P1_1") (pintype "passive"))
      (node (ref "K1") (pin "2") (pinfunction "P2_2") (pintype "passive"))
      (node (ref "K2") (pin "1") (pinfunction "1_1") (pintype "bidirectional"))
      (node (ref "R1") (pin "1") (pinfunction "1_1") (pintype "passive"))
      (node (ref "R11") (pin "1") (pinfunction "1_1") (pintype "passive"))
      (node (ref "R16") (pin "1") (pinfunction "1_1") (pintype "passive"))
      (node (ref "R17") (pin "1") (pinfunction "1_1") (pintype "passive"))
      (node (ref "R2") (pin "1") (pinfunction "1_1") (pintype "passive"))
      (node (ref "R6") (pin "2") (pinfunction "2_2") (pintype "passive"))
      (node (ref "TP4") (pin "TP") (pinfunction "TP_TP") (pintype "input"))
      (node (ref "U1") (pin "1") (pinfunction "GND_1") (pintype "power_in"))
      (node (ref "U1") (pin "1.1") (pinfunction "GND_1.1") (pintype "power_in"))
      (node (ref "U1") (pin "1.2") (pinfunction "GND_1.2") (pintype "power_in"))
      (node (ref "U1") (pin "15") (pinfunction "GND_15") (pintype "power_in"))
      (node (ref "U1") (pin "38") (pinfunction "GND_38") (pintype "power_in"))
      (node (ref "U2") (pin "2") (pinfunction "GND_2") (pintype "power_in"))
      (node (ref "U2") (pin "25") (pinfunction "GND_25") (pintype "power_in"))
      (node (ref "U3") (pin "1") (pinfunction "ADJ_1") (pintype "input"))
      (node (ref "U4") (pin "1") (pinfunction "ADJ_1") (pintype "input"))
      (node (ref "U5") (pin "2") (pinfunction "2_2") (pintype "bidirectional"))
      (node (ref "USB1") (pin "A1") (pinfunction "GND1_A1") (pintype "passive"))
      (node (ref "USB1") (pin "A12") (pinfunction "GND2_A12") (pintype "passive"))
      (node (ref "USB1") (pin "B1") (pinfunction "GND3_B1") (pintype "passive"))
      (node (ref "USB1") (pin "B12") (pinfunction "GND4_B12") (pintype "passive"))
      (node (ref "USB1") (pin "S1") (pinfunction "SHIELD_S1") (pintype "passive"))
      (node (ref "USB1") (pin "S2") (pinfunction "SHIELD_S2") (pintype "passive"))
      (node (ref "USB1") (pin "S3") (pinfunction "SHIELD_S3") (pintype "passive"))
      (node (ref "USB1") (pin "S4") (pinfunction "SHIELD_S4") (pintype "passive"))
      (node (ref "USB2") (pin "GND") (pinfunction "GND_GND") (pintype "bidirectional"))
    )
    (net (code "8") (name "IO0") (class "Default")
      (node (ref "C7") (pin "2") (pinfunction "2_2") (pintype "passive"))
      (node (ref "J4") (pin "8") (pinfunction "8_8") (pintype "passive"))
      (node (ref "J5") (pin "4") (pinfunction "4_4") (pintype "bidirectional"))
      (node (ref "K2") (pin "2") (pinfunction "2_2") (pintype "bidirectional"))
      (node (ref "Q2") (pin "3") (pinfunction "C_3") (pintype "passive"))
      (node (ref "R8") (pin "1") (pinfunction "1_1") (pintype "passive"))
      (node (ref "U1") (pin "25") (pinfunction "IO0_25") (pintype "bidirectional"))
    )
    (net (code "9") (name "IO2") (class "Default")
      (node (ref "J1") (pin "3") (pinfunction "3_3") (pintype "passive"))
      (node (ref "R12") (pin "1") (pinfunction "1_1") (pintype "passive"))
      (node (ref "U1") (pin "24") (pinfunction "IO2_24") (pintype "bidirectional"))
    )
    (net (code "10") (name "IO4") (class "Default")
      (node (ref "J4") (pin "11") (pinfunction "11_11") (pintype "passive"))
      (node (ref "U1") (pin "26") (pinfunction "IO4_26") (pintype "bidirectional"))
    )
    (net (code "11") (name "IO5") (class "Default")
      (node (ref "J2") (pin "3") (pinfunction "3_3") (pintype "passive"))
      (node (ref "U1") (pin "29") (pinfunction "IO5_29") (pintype "bidirectional"))
    )
    (net (code "12") (name "IO12") (class "Default")
      (node (ref "J1") (pin "6") (pinfunction "6_6") (pintype "passive"))
      (node (ref "U1") (pin "14") (pinfunction "IO12_14") (pintype "bidirectional"))
    )
    (net (code "13") (name "IO13") (class "Default")
      (node (ref "J1") (pin "5") (pinfunction "5_5") (pintype "passive"))
      (node (ref "U1") (pin "16") (pinfunction "IO13_16") (pintype "bidirectional"))
    )
    (net (code "14") (name "IO14") (class "Default")
      (node (ref "J1") (pin "7") (pinfunction "7_7") (pintype "passive"))
      (node (ref "U1") (pin "13") (pinfunction "IO14_13") (pintype "bidirectional"))
    )
    (net (code "15") (name "IO15") (class "Default")
      (node (ref "J1") (pin "4") (pinfunction "4_4") (pintype "passive"))
      (node (ref "R16") (pin "2") (pinfunction "2_2") (pintype "passive"))
      (node (ref "U1") (pin "23") (pinfunction "IO15_23") (pintype "bidirectional"))
    )
    (net (code "16") (name "IO16") (class "Default")
      (node (ref "J1") (pin "1") (pinfunction "1_1") (pintype "passive"))
      (node (ref "U1") (pin "27") (pinfunction "IO16_27") (pintype "bidirectional"))
    )
    (net (code "17") (name "IO17") (class "Default")
      (node (ref "J1") (pin "2") (pinfunction "2_2") (pintype "passive"))
      (node (ref "U1") (pin "28") (pinfunction "IO17_28") (pintype "bidirectional"))
    )
    (net (code "18") (name "IO18") (class "Default")
      (node (ref "J2") (pin "6") (pinfunction "6_6") (pintype "passive"))
      (node (ref "U1") (pin "30") (pinfunction "IO18_30") (pintype "bidirectional"))
    )
    (net (code "19") (name "IO19") (class "Default")
      (node (ref "J2") (pin "5") (pinfunction "5_5") (pintype "passive"))
      (node (ref "U1") (pin "31") (pinfunction "IO19_31") (pintype "bidirectional"))
    )
    (net (code "20") (name "IO21") (class "Default")
      (node (ref "J2") (pin "9") (pinfunction "9_9") (pintype "passive"))
      (node (ref "J6") (pin "2") (pinfunction "2_2") (pintype "bidirectional"))
      (node (ref "J7") (pin "3") (pinfunction "3_3") (pintype "passive"))
      (node (ref "R13") (pin "1") (pinfunction "1_1") (pintype "passive"))
      (node (ref "U1") (pin "33") (pinfunction "IO21_33") (pintype "bidirectional"))
    )
    (net (code "21") (name "IO22") (class "Default")
      (node (ref "J2") (pin "10") (pinfunction "10_10") (pintype "passive"))
      (node (ref "J6") (pin "1") (pinfunction "1_1") (pintype "bidirectional"))
      (node (ref "J7") (pin "4") (pinfunction "4_4") (pintype "passive"))
      (node (ref "R14") (pin "1") (pinfunction "1_1") (pintype "passive"))
      (node (ref "U1") (pin "36") (pinfunction "IO22_36") (pintype "bidirectional"))
    )
    (net (code "22") (name "IO23") (class "Default")
      (node (ref "J2") (pin "4") (pinfunction "4_4") (pintype "passive"))
      (node (ref "U1") (pin "37") (pinfunction "IO23_37") (pintype "bidirectional"))
    )
    (net (code "23") (name "IO25") (class "Default")
      (node (ref "J3") (pin "2") (pinfunction "2_2") (pintype "passive"))
      (node (ref "U1") (pin "10") (pinfunction "IO25_10") (pintype "bidirectional"))
    )
    (net (code "24") (name "IO26") (class "Default")
      (node (ref "J3") (pin "1") (pinfunction "1_1") (pintype "passive"))
      (node (ref "U1") (pin "11") (pinfunction "IO26_11") (pintype "bidirectional"))
    )
    (net (code "25") (name "IO27") (class "Default")
      (node (ref "J1") (pin "8") (pinfunction "8_8") (pintype "passive"))
      (node (ref "U1") (pin "12") (pinfunction "IO27_12") (pintype "bidirectional"))
    )
    (net (code "26") (name "IO32") (class "Default")
      (node (ref "J2") (pin "2") (pinfunction "2_2") (pintype "passive"))
      (node (ref "U1") (pin "8") (pinfunction "IO32_8") (pintype "bidirectional"))
    )
    (net (code "27") (name "IO33") (class "Default")
      (node (ref "J2") (pin "1") (pinfunction "1_1") (pintype "passive"))
      (node (ref "U1") (pin "9") (pinfunction "IO33_9") (pintype "bidirectional"))
    )
    (net (code "28") (name "IO34") (class "Default")
      (node (ref "J3") (pin "4") (pinfunction "4_4") (pintype "passive"))
      (node (ref "U1") (pin "6") (pinfunction "IO34_6") (pintype "bidirectional"))
    )
    (net (code "29") (name "IO35") (class "Default")
      (node (ref "J3") (pin "3") (pinfunction "3_3") (pintype "passive"))
      (node (ref "U1") (pin "7") (pinfunction "IO35_7") (pintype "bidirectional"))
    )
    (net (code "30") (name "IO36") (class "Default")
      (node (ref "J3") (pin "6") (pinfunction "6_6") (pintype "passive"))
      (node (ref "U1") (pin "4") (pinfunction "SENSOR_VP_4") (pintype "input"))
    )
    (net (code "31") (name "IO39") (class "Default")
      (node (ref "J3") (pin "5") (pinfunction "5_5") (pintype "passive"))
      (node (ref "U1") (pin "5") (pinfunction "SENSOR_VN_5") (pintype "input"))
    )
    (net (code "32") (name "Net-(D3-K)") (class "Default")
      (node (ref "C23") (pin "2") (pinfunction "2_2") (pintype "passive"))
      (node (ref "C24") (pin "2") (pinfunction "2_2") (pintype "passive"))
      (node (ref "D3") (pin "1") (pinfunction "K_1") (pintype "bidirectional"))
      (node (ref "D4") (pin "C") (pinfunction "-_C") (pintype "passive"))
      (node (ref "Q5") (pin "2") (pinfunction "S_2") (pintype "passive"))
      (node (ref "U4") (pin "3") (pinfunction "IN_3") (pintype "input"))
    )
    (net (code "33") (name "Net-(D4-+)") (class "Default")
      (node (ref "D4") (pin "A") (pinfunction "+_A") (pintype "passive"))
      (node (ref "Q5") (pin "1") (pinfunction "G_1") (pintype "passive"))
      (node (ref "R17") (pin "2") (pinfunction "2_2") (pintype "passive"))
    )
    (net (code "34") (name "Net-(LED1-Pad-)") (class "Default")
      (node (ref "LED1") (pin "-") (pinfunction "-_-") (pintype "passive"))
      (node (ref "R11") (pin "2") (pinfunction "2_2") (pintype "passive"))
    )
    (net (code "35") (name "Net-(LED2-Pad-)") (class "Default")
      (node (ref "LED2") (pin "-") (pinfunction "-_-") (pintype "passive"))
      (node (ref "R12") (pin "2") (pinfunction "2_2") (pintype "passive"))
    )
    (net (code "36") (name "Net-(Q1-B)") (class "Default")
      (node (ref "Q1") (pin "1") (pinfunction "B_1") (pintype "passive"))
      (node (ref "R9") (pin "2") (pinfunction "2_2") (pintype "passive"))
    )
    (net (code "37") (name "Net-(Q2-B)") (class "Default")
      (node (ref "Q2") (pin "1") (pinfunction "B_1") (pintype "passive"))
      (node (ref "R10") (pin "2") (pinfunction "2_2") (pintype "passive"))
    )
    (net (code "38") (name "Net-(U2-D+)") (class "Default")
      (node (ref "R3") (pin "2") (pinfunction "2_2") (pintype "passive"))
      (node (ref "U2") (pin "3") (pinfunction "D+_3") (pintype "bidirectional"))
    )
    (net (code "39") (name "Net-(U2-D-)") (class "Default")
      (node (ref "R4") (pin "2") (pinfunction "2_2") (pintype "passive"))
      (node (ref "U2") (pin "4") (pinfunction "D-_4") (pintype "bidirectional"))
    )
    (net (code "40") (name "Net-(U2-VBUS)") (class "Default")
      (node (ref "R5") (pin "1") (pinfunction "1_1") (pintype "passive"))
      (node (ref "R6") (pin "1") (pinfunction "1_1") (pintype "passive"))
      (node (ref "U2") (pin "8") (pinfunction "VBUS_8") (pintype "input"))
    )
    (net (code "41") (name "Net-(U2-VPP)") (class "Default")
      (node (ref "C8") (pin "2") (pinfunction "2_2") (pintype "passive"))
      (node (ref "U2") (pin "16") (pinfunction "VPP_16") (pintype "passive"))
    )
    (net (code "42") (name "Net-(U2-~{RST})") (class "Default")
      (node (ref "R7") (pin "2") (pinfunction "2_2") (pintype "passive"))
      (node (ref "U2") (pin "9") (pinfunction "~{RST}_9") (pintype "input"))
    )
    (net (code "43") (name "Net-(U3-IN)") (class "Default")
      (node (ref "C15") (pin "2") (pinfunction "2_2") (pintype "passive"))
      (node (ref "C18") (pin "2") (pinfunction "2_2") (pintype "passive"))
      (node (ref "F1") (pin "2") (pinfunction "2_2") (pintype "bidirectional"))
      (node (ref "U3") (pin "3") (pinfunction "IN_3") (pintype "input"))
    )
    (net (code "44") (name "Net-(USB1-CC1)") (class "Default")
      (node (ref "R1") (pin "2") (pinfunction "2_2") (pintype "passive"))
      (node (ref "TP5") (pin "TP") (pinfunction "TP_TP") (pintype "input"))
      (node (ref "USB1") (pin "A5") (pinfunction "CC1_A5") (pintype "passive"))
    )
    (net (code "45") (name "Net-(USB1-CC2)") (class "Default")
      (node (ref "R2") (pin "2") (pinfunction "2_2") (pintype "passive"))
      (node (ref "TP6") (pin "TP") (pinfunction "TP_TP") (pintype "input"))
      (node (ref "USB1") (pin "B5") (pinfunction "CC2_B5") (pintype "passive"))
    )
    (net (code "46") (name "RTS") (class "Default")
      (node (ref "Q1") (pin "2") (pinfunction "E_2") (pintype "passive"))
      (node (ref "R10") (pin "1") (pinfunction "1_1") (pintype "passive"))
      (node (ref "U2") (pin "19") (pinfunction "RTS_19") (pintype "output"))
    )
    (net (code "47") (name "RXD") (class "Default")
      (node (ref "J4") (pin "9") (pinfunction "9_9") (pintype "passive"))
      (node (ref "J5") (pin "3") (pinfunction "3_3") (pintype "bidirectional"))
      (node (ref "U1") (pin "34") (pinfunction "RXD0_34") (pintype "bidirectional"))
      (node (ref "U2") (pin "21") (pinfunction "TXD_21") (pintype "output"))
    )
    (net (code "48") (name "TXD") (class "Default")
      (node (ref "J4") (pin "10") (pinfunction "10_10") (pintype "passive"))
      (node (ref "J5") (pin "1") (pinfunction "1_1") (pintype "bidirectional"))
      (node (ref "U1") (pin "35") (pinfunction "TXD0_35") (pintype "bidirectional"))
      (node (ref "U2") (pin "20") (pinfunction "RXD_20") (pintype "input"))
    )
    (net (code "49") (name "VCCIO") (class "Default")
      (node (ref "C19") (pin "2") (pinfunction "2_2") (pintype "passive"))
      (node (ref "C20") (pin "2") (pinfunction "2_2") (pintype "passive"))
      (node (ref "C21") (pin "2") (pinfunction "2_2") (pintype "passive"))
      (node (ref "D1") (pin "2") (pinfunction "A_2") (pintype "bidirectional"))
      (node (ref "D2") (pin "2") (pinfunction "A_2") (pintype "bidirectional"))
      (node (ref "Q3") (pin "1") (pinfunction "G_1") (pintype "passive"))
      (node (ref "Q4") (pin "1") (pinfunction "G_1") (pintype "passive"))
      (node (ref "U4") (pin "2") (pinfunction "OUT_2") (pintype "output"))
      (node (ref "U4") (pin "4") (pinfunction "OUT_4") (pintype "output"))
    )
    (net (code "50") (name "VIN") (class "Default")
      (node (ref "C25") (pin "2") (pinfunction "2_2") (pintype "passive"))
      (node (ref "C26") (pin "2") (pinfunction "2_2") (pintype "passive"))
      (node (ref "C32") (pin "2") (pinfunction "2_2") (pintype "passive"))
      (node (ref "D2") (pin "1") (pinfunction "K_1") (pintype "bidirectional"))
      (node (ref "D3") (pin "2") (pinfunction "A_2") (pintype "bidirectional"))
      (node (ref "J4") (pin "1") (pinfunction "1_1") (pintype "passive"))
      (node (ref "Q4") (pin "2") (pinfunction "S_2") (pintype "passive"))
      (node (ref "Q5") (pin "3") (pinfunction "D_3") (pintype "passive"))
    )
    (net (code "51") (name "V_USB") (class "Default")
      (node (ref "C1") (pin "2") (pinfunction "2_2") (pintype "passive"))
      (node (ref "Q3") (pin "3") (pinfunction "D_3") (pintype "passive"))
      (node (ref "Q4") (pin "3") (pinfunction "D_3") (pintype "passive"))
      (node (ref "R5") (pin "2") (pinfunction "2_2") (pintype "passive"))
      (node (ref "TP1") (pin "TP") (pinfunction "TP_TP") (pintype "input"))
      (node (ref "U5") (pin "5") (pinfunction "5_5") (pintype "bidirectional"))
      (node (ref "USB1") (pin "A4") (pinfunction "VBUS1_A4") (pintype "passive"))
      (node (ref "USB1") (pin "A9") (pinfunction "VBUS2_A9") (pintype "passive"))
      (node (ref "USB1") (pin "B4") (pinfunction "VBUS3_B4") (pintype "passive"))
      (node (ref "USB1") (pin "B9") (pinfunction "VBUS4_B9") (pintype "passive"))
      (node (ref "USB2") (pin "VBUS") (pinfunction "VBUS_VBUS") (pintype "bidirectional"))
    )
    (net (code "52") (name "unconnected-(J4-Pad12)") (class "Default")
      (node (ref "J4") (pin "12") (pinfunction "12_12") (pintype "passive"))
    )
    (net (code "53") (name "unconnected-(K1-G-Pad5)") (class "Default")
      (node (ref "K1") (pin "5") (pinfunction "G_5") (pintype "passive"))
    )
    (net (code "54") (name "unconnected-(U1-SCK{slash}CLK-Pad20)") (class "Default")
      (node (ref "U1") (pin "20") (pinfunction "SCK/CLK_20") (pintype "bidirectional"))
    )
    (net (code "55") (name "unconnected-(U1-SCS{slash}CMD-Pad19)") (class "Default")
      (node (ref "U1") (pin "19") (pinfunction "SCS/CMD_19") (pintype "bidirectional"))
    )
    (net (code "56") (name "unconnected-(U1-SDI{slash}SD1-Pad22)") (class "Default")
      (node (ref "U1") (pin "22") (pinfunction "SDI/SD1_22") (pintype "bidirectional"))
    )
    (net (code "57") (name "unconnected-(U1-SDO{slash}SD0-Pad21)") (class "Default")
      (node (ref "U1") (pin "21") (pinfunction "SDO/SD0_21") (pintype "bidirectional"))
    )
    (net (code "58") (name "unconnected-(U1-SHD{slash}SD2-Pad17)") (class "Default")
      (node (ref "U1") (pin "17") (pinfunction "SHD/SD2_17") (pintype "bidirectional"))
    )
    (net (code "59") (name "unconnected-(U1-SWP{slash}SD3-Pad18)") (class "Default")
      (node (ref "U1") (pin "18") (pinfunction "SWP/SD3_18") (pintype "bidirectional"))
    )
    (net (code "60") (name "unconnected-(U2-CTS-Pad18)") (class "Default")
      (node (ref "U2") (pin "18") (pinfunction "CTS_18") (pintype "input"))
    )
    (net (code "61") (name "unconnected-(U2-DCD-Pad24)") (class "Default")
      (node (ref "U2") (pin "24") (pinfunction "DCD_24") (pintype "input"))
    )
    (net (code "62") (name "unconnected-(U2-DSR-Pad22)") (class "Default")
      (node (ref "U2") (pin "22") (pinfunction "DSR_22") (pintype "input"))
    )
    (net (code "63") (name "unconnected-(U2-GPIO.0-Pad14)") (class "Default")
      (node (ref "U2") (pin "14") (pinfunction "GPIO.0_14") (pintype "bidirectional"))
    )
    (net (code "64") (name "unconnected-(U2-GPIO.1-Pad13)") (class "Default")
      (node (ref "U2") (pin "13") (pinfunction "GPIO.1_13") (pintype "bidirectional"))
    )
    (net (code "65") (name "unconnected-(U2-GPIO.2-Pad12)") (class "Default")
      (node (ref "U2") (pin "12") (pinfunction "GPIO.2_12") (pintype "bidirectional"))
    )
    (net (code "66") (name "unconnected-(U2-GPIO.3-Pad11)") (class "Default")
      (node (ref "U2") (pin "11") (pinfunction "GPIO.3_11") (pintype "bidirectional"))
    )
    (net (code "67") (name "unconnected-(U2-NC-Pad10)") (class "Default")
      (node (ref "U2") (pin "10") (pinfunction "NC_10") (pintype "bidirectional"))
    )
    (net (code "68") (name "unconnected-(U2-RI-Pad1)") (class "Default")
      (node (ref "U2") (pin "1") (pinfunction "RI_1") (pintype "input"))
    )
    (net (code "69") (name "unconnected-(U2-SUSPEND-Pad17)") (class "Default")
      (node (ref "U2") (pin "17") (pinfunction "SUSPEND_17") (pintype "output"))
    )
    (net (code "70") (name "unconnected-(U2-~{SUSPEND}-Pad15)") (class "Default")
      (node (ref "U2") (pin "15") (pinfunction "~{SUSPEND}_15") (pintype "output"))
    )
    (net (code "71") (name "unconnected-(USB1-RX1+-PadB11)") (class "Default")
      (node (ref "USB1") (pin "B11") (pinfunction "RX1+_B11") (pintype "passive"))
    )
    (net (code "72") (name "unconnected-(USB1-RX1--PadB10)") (class "Default")
      (node (ref "USB1") (pin "B10") (pinfunction "RX1-_B10") (pintype "passive"))
    )
    (net (code "73") (name "unconnected-(USB1-RX2+-PadA11)") (class "Default")
      (node (ref "USB1") (pin "A11") (pinfunction "RX2+_A11") (pintype "passive"))
    )
    (net (code "74") (name "unconnected-(USB1-RX2--PadA10)") (class "Default")
      (node (ref "USB1") (pin "A10") (pinfunction "RX2-_A10") (pintype "passive"))
    )
    (net (code "75") (name "unconnected-(USB1-SBU1-PadA8)") (class "Default")
      (node (ref "USB1") (pin "A8") (pinfunction "SBU1_A8") (pintype "passive"))
    )
    (net (code "76") (name "unconnected-(USB1-SBU2-PadB8)") (class "Default")
      (node (ref "USB1") (pin "B8") (pinfunction "SBU2_B8") (pintype "passive"))
    )
    (net (code "77") (name "unconnected-(USB1-TX1+-PadA2)") (class "Default")
      (node (ref "USB1") (pin "A2") (pinfunction "TX1+_A2") (pintype "passive"))
    )
    (net (code "78") (name "unconnected-(USB1-TX1--PadA3)") (class "Default")
      (node (ref "USB1") (pin "A3") (pinfunction "TX1-_A3") (pintype "passive"))
    )
    (net (code "79") (name "unconnected-(USB1-TX2+-PadB2)") (class "Default")
      (node (ref "USB1") (pin "B2") (pinfunction "TX2+_B2") (pintype "passive"))
    )
    (net (code "80") (name "unconnected-(USB1-TX2--PadB3)") (class "Default")
      (node (ref "USB1") (pin "B3") (pinfunction "TX2-_B3") (pintype "passive"))
    )
  )
)
